# 03_-_POWER.net
KiCad netlist of a schematic drawn in Altium Designer
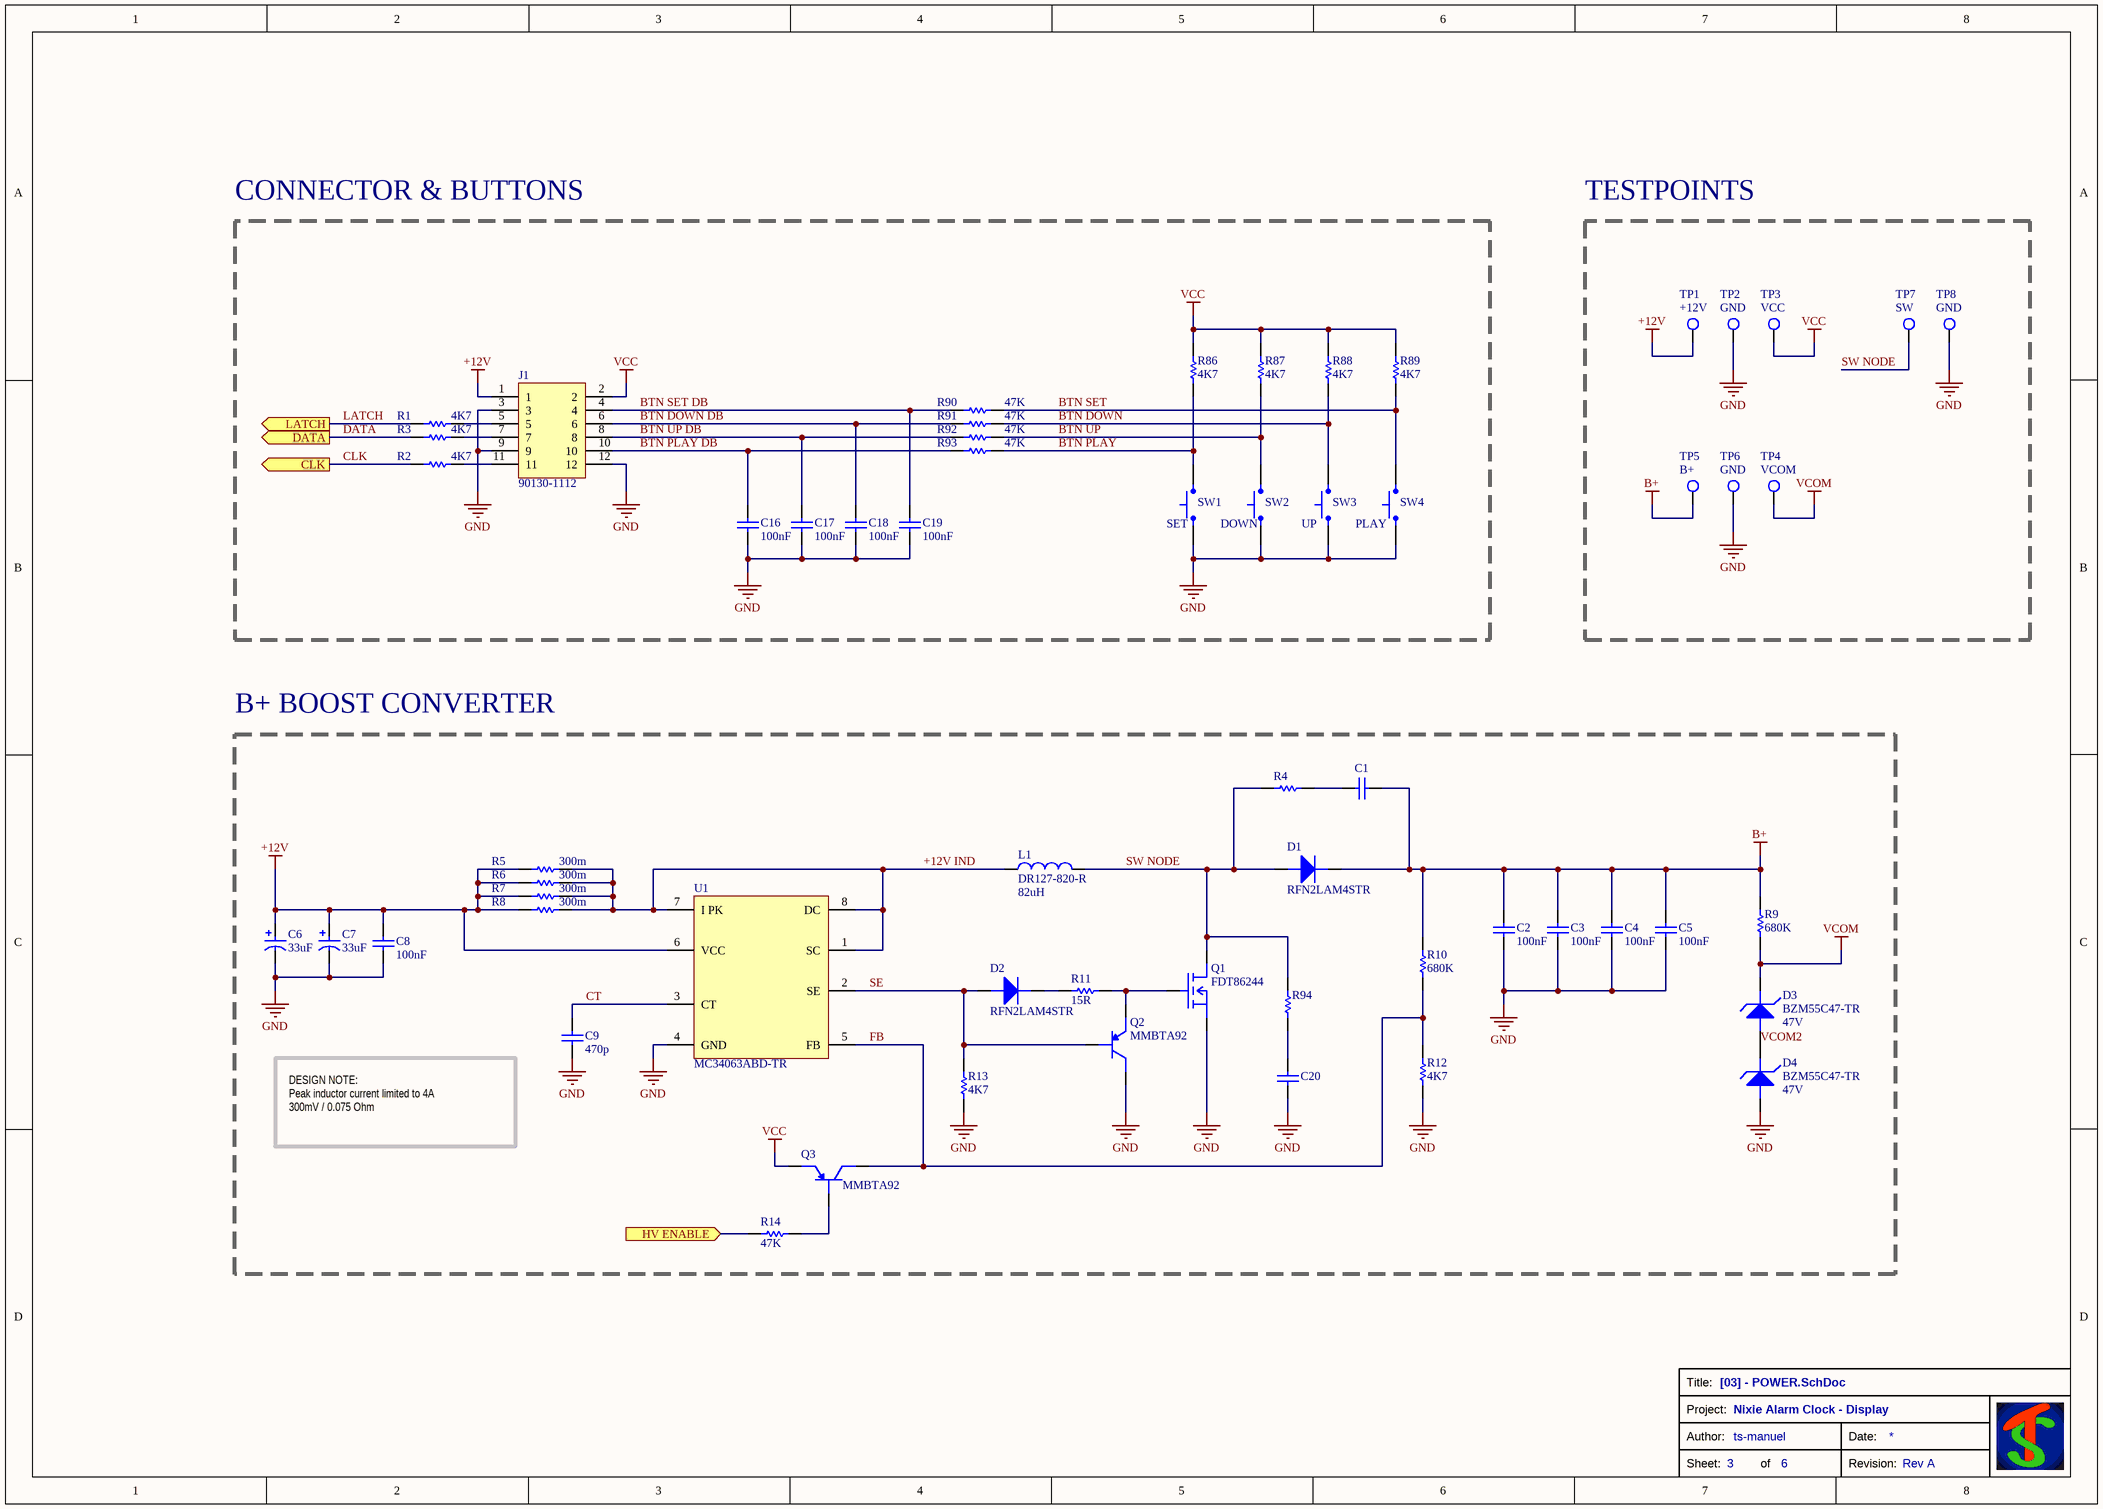
[diagram p0: [03] - POWER.SchDoc]

(export (version "E")
  (design (tool "Eeschema 10.0.6"))
  (components
    (comp (ref "C1")
      (value "885342208002")
      (footprint "CAP-1206")
      (description "Condensatori in ceramica multistrato MLCC - SMD/SMT WCAP-CSMH 200V 0.1uF 1206 10%")
      (fields (field (name "MANUFACTURER") "Wurth Elektronik") (field (name "TOLERANCE") "10%"))
      (libsource (lib "mt_local_library") (part "CAP-1206-100n-885342208002"))
    )
    (comp (ref "C2")
      (value "100nF")
      (footprint "CAP-1206")
      (description "Condensatori in ceramica multistrato MLCC - SMD/SMT WCAP-CSMH 200V 0.1uF 1206 10%")
      (fields (field (name "MANUFACTURER") "Wurth Elektronik") (field (name "TOLERANCE") "10%"))
      (libsource (lib "mt_local_library") (part "CAP-1206-100n-885342208002"))
    )
    (comp (ref "C3")
      (value "100nF")
      (footprint "CAP-1206")
      (description "Condensatori in ceramica multistrato MLCC - SMD/SMT WCAP-CSMH 200V 0.1uF 1206 10%")
      (fields (field (name "MANUFACTURER") "Wurth Elektronik") (field (name "TOLERANCE") "10%"))
      (libsource (lib "mt_local_library") (part "CAP-1206-100n-885342208002"))
    )
    (comp (ref "C4")
      (value "100nF")
      (footprint "CAP-1206")
      (description "Condensatori in ceramica multistrato MLCC - SMD/SMT WCAP-CSMH 200V 0.1uF 1206 10%")
      (fields (field (name "MANUFACTURER") "Wurth Elektronik") (field (name "TOLERANCE") "10%"))
      (libsource (lib "mt_local_library") (part "CAP-1206-100n-885342208002"))
    )
    (comp (ref "C5")
      (value "100nF")
      (footprint "CAP-1206")
      (description "Condensatori in ceramica multistrato MLCC - SMD/SMT WCAP-CSMH 200V 0.1uF 1206 10%")
      (fields (field (name "MANUFACTURER") "Wurth Elektronik") (field (name "TOLERANCE") "10%"))
      (libsource (lib "mt_local_library") (part "CAP-1206-100n-885342208002"))
    )
    (comp (ref "C6")
      (value "33uF")
      (footprint "CAPAE7366X60M")
      (description "Condensatori a polimeri organici in alluminio 40V 33uF 20% ESR=45mOhms")
      (fields (field (name "MANUFACTURER") "KEMET") (field (name "TOLERANCE") "20%"))
      (libsource (lib "mt_local_library") (part "CAP-CAN-33u-A768EB336M1GLAE045"))
    )
    (comp (ref "C7")
      (value "33uF")
      (footprint "CAPAE7366X60M")
      (description "Condensatori a polimeri organici in alluminio 40V 33uF 20% ESR=45mOhms")
      (fields (field (name "MANUFACTURER") "KEMET") (field (name "TOLERANCE") "20%"))
      (libsource (lib "mt_local_library") (part "CAP-CAN-33u-A768EB336M1GLAE045"))
    )
    (comp (ref "C8")
      (value "100nF")
      (footprint "CAP-1206")
      (description "Condensatori in ceramica multistrato MLCC - SMD/SMT WCAP-CSMH 200V 0.1uF 1206 10%")
      (fields (field (name "MANUFACTURER") "Wurth Elektronik") (field (name "TOLERANCE") "10%"))
      (libsource (lib "mt_local_library") (part "CAP-1206-100n-885342208002"))
    )
    (comp (ref "C9")
      (value "470p")
      (footprint "CAP-0805")
      (description "Condensatori in ceramica multistrato MLCC - SMD/SMT 0805 470pF 100volts C0G 5%")
      (fields (field (name "MANUFACTURER") "Wurth Elektronik") (field (name "TOLERANCE") "20%"))
      (libsource (lib "mt_local_library") (part "CAP-0805-470p-VJ0805A471JXBCW1BC"))
    )
    (comp (ref "C16")
      (value "100nF")
      (footprint "CAP-1206")
      (description "Condensatori in ceramica multistrato MLCC - SMD/SMT WCAP-CSMH 200V 0.1uF 1206 10%")
      (fields (field (name "MANUFACTURER") "Wurth Elektronik") (field (name "TOLERANCE") "10%"))
      (libsource (lib "mt_local_library") (part "CAP-1206-100n-885342208002"))
    )
    (comp (ref "C17")
      (value "100nF")
      (footprint "CAP-1206")
      (description "Condensatori in ceramica multistrato MLCC - SMD/SMT WCAP-CSMH 200V 0.1uF 1206 10%")
      (fields (field (name "MANUFACTURER") "Wurth Elektronik") (field (name "TOLERANCE") "10%"))
      (libsource (lib "mt_local_library") (part "CAP-1206-100n-885342208002"))
    )
    (comp (ref "C18")
      (value "100nF")
      (footprint "CAP-1206")
      (description "Condensatori in ceramica multistrato MLCC - SMD/SMT WCAP-CSMH 200V 0.1uF 1206 10%")
      (fields (field (name "MANUFACTURER") "Wurth Elektronik") (field (name "TOLERANCE") "10%"))
      (libsource (lib "mt_local_library") (part "CAP-1206-100n-885342208002"))
    )
    (comp (ref "C19")
      (value "100nF")
      (footprint "CAP-1206")
      (description "Condensatori in ceramica multistrato MLCC - SMD/SMT WCAP-CSMH 200V 0.1uF 1206 10%")
      (fields (field (name "MANUFACTURER") "Wurth Elektronik") (field (name "TOLERANCE") "10%"))
      (libsource (lib "mt_local_library") (part "CAP-1206-100n-885342208002"))
    )
    (comp (ref "C20")
      (value "885342208002")
      (footprint "CAP-1206")
      (description "Condensatori in ceramica multistrato MLCC - SMD/SMT WCAP-CSMH 200V 0.1uF 1206 10%")
      (fields (field (name "MANUFACTURER") "Wurth Elektronik") (field (name "TOLERANCE") "10%"))
      (libsource (lib "mt_local_library") (part "CAP-1206-100n-885342208002"))
    )
    (comp (ref "D1")
      (value "RFN2LAM4STR")
      (footprint "SODFL472X100-2M")
      (description "Diodi - Uso generico, alimentazione, commutazione 400V 1.5A Io PMDTM")
      (libsource (lib "mt_local_library") (part "DIODE-RFN2LAM4STR"))
    )
    (comp (ref "D2")
      (value "RFN2LAM4STR")
      (footprint "SODFL472X100-2M")
      (description "Diodi - Uso generico, alimentazione, commutazione 400V 1.5A Io PMDTM")
      (libsource (lib "mt_local_library") (part "DIODE-RFN2LAM4STR"))
    )
    (comp (ref "D3")
      (value "BZM55C47-TR")
      (footprint "DIOMELF1913M")
      (description "Diodi Zener 47 Volt 0.5W 5%")
      (fields (field (name "ZENER VOLTAGE") "47V"))
      (libsource (lib "mt_local_library") (part "ZENER-47V-BZM55C47-TR"))
    )
    (comp (ref "D4")
      (value "BZM55C47-TR")
      (footprint "DIOMELF1913M")
      (description "Diodi Zener 47 Volt 0.5W 5%")
      (fields (field (name "ZENER VOLTAGE") "47V"))
      (libsource (lib "mt_local_library") (part "ZENER-47V-BZM55C47-TR"))
    )
    (comp (ref "J1")
      (value "90130-1112")
      (footprint "SHDR12W65P254_2X6_1758X975X1110P")
      (description "Terminali e capicorda 2.54MM CGRIDIII HDR 12P V DR SHRD TIN")
      (libsource (lib "mt_local_library") (part "HEADER-12x2-2.54-TH-90130-1112"))
    )
    (comp (ref "L1")
      (value "DR127-820-R")
      (footprint "IND-DR127")
      (description "Induttori fissi 82uH 4.0A 0.143ohms")
      (fields
        (field (name "MANUFACTURER") "Taiyo Yuden")
        (field (name "TOLERANCE") "30%")
        (field (name "ALTIUM_VALUE") "82uH")
      )
      (libsource (lib "mt_local_library") (part "IND-DR127-82u"))
    )
    (comp (ref "Q1")
      (value "FDT86244")
      (footprint "SOT230P700X180-4M")
      (description "MOSFET 150V N-Channel PowerTrench MOSFET")
      (libsource (lib "mt_local_library") (part "NMOS-FDT86244"))
    )
    (comp (ref "Q2")
      (value "MMBTA92")
      (footprint "SOT95P240X110-3N")
      (description "300V PNP SMALL SIGNAL TRANSISTOR IN SOT23")
      (libsource (lib "mt_local_library") (part "PNP-MMBTA92"))
    )
    (comp (ref "Q3")
      (value "MMBTA92")
      (footprint "SOT95P240X110-3N")
      (description "300V PNP SMALL SIGNAL TRANSISTOR IN SOT23")
      (libsource (lib "mt_local_library") (part "PNP-MMBTA92"))
    )
    (comp (ref "R1")
      (value "4K7")
      (footprint "RES-0805")
      (description "Thin Film Resistors 4.7K ohm 1% 50 ppm")
      (fields (field (name "MANUFACTURER") "Yageo") (field (name "TOLERANCE") "1%"))
      (libsource (lib "mt_local_library") (part "RES-0805-4K7-RT0805FRE134K7L"))
    )
    (comp (ref "R2")
      (value "4K7")
      (footprint "RES-0805")
      (description "Thin Film Resistors 4.7K ohm 1% 50 ppm")
      (fields (field (name "MANUFACTURER") "Yageo") (field (name "TOLERANCE") "1%"))
      (libsource (lib "mt_local_library") (part "RES-0805-4K7-RT0805FRE134K7L"))
    )
    (comp (ref "R3")
      (value "4K7")
      (footprint "RES-0805")
      (description "Thin Film Resistors 4.7K ohm 1% 50 ppm")
      (fields (field (name "MANUFACTURER") "Yageo") (field (name "TOLERANCE") "1%"))
      (libsource (lib "mt_local_library") (part "RES-0805-4K7-RT0805FRE134K7L"))
    )
    (comp (ref "R4")
      (value "RT1206FRE07680KL")
      (footprint "RES-1206")
      (description "Thin Film Resistors 680K OHM 1% 50PPM 1/4W")
      (fields (field (name "MANUFACTURER") "Yageo") (field (name "TOLERANCE") "1%"))
      (libsource (lib "mt_local_library") (part "RES-1206-680K-RT1206FRE07680KL"))
    )
    (comp (ref "R5")
      (value "300m")
      (footprint "RES-0805")
      (description "Resistori a pellicola spessa - SMD 0805 0.25W 1% .30ohms AEC-Q200")
      (fields (field (name "MANUFACTURER") "Yageo") (field (name "TOLERANCE") "1%"))
      (libsource (lib "mt_local_library") (part "RES-0805-300m-ERJ-U6QFR30V"))
    )
    (comp (ref "R6")
      (value "300m")
      (footprint "RES-0805")
      (description "Resistori a pellicola spessa - SMD 0805 0.25W 1% .30ohms AEC-Q200")
      (fields (field (name "MANUFACTURER") "Yageo") (field (name "TOLERANCE") "1%"))
      (libsource (lib "mt_local_library") (part "RES-0805-300m-ERJ-U6QFR30V"))
    )
    (comp (ref "R7")
      (value "300m")
      (footprint "RES-0805")
      (description "Resistori a pellicola spessa - SMD 0805 0.25W 1% .30ohms AEC-Q200")
      (fields (field (name "MANUFACTURER") "Yageo") (field (name "TOLERANCE") "1%"))
      (libsource (lib "mt_local_library") (part "RES-0805-300m-ERJ-U6QFR30V"))
    )
    (comp (ref "R8")
      (value "300m")
      (footprint "RES-0805")
      (description "Resistori a pellicola spessa - SMD 0805 0.25W 1% .30ohms AEC-Q200")
      (fields (field (name "MANUFACTURER") "Yageo") (field (name "TOLERANCE") "1%"))
      (libsource (lib "mt_local_library") (part "RES-0805-300m-ERJ-U6QFR30V"))
    )
    (comp (ref "R9")
      (value "680K")
      (footprint "RES-1206")
      (description "Thin Film Resistors 680K OHM 1% 50PPM 1/4W")
      (fields (field (name "MANUFACTURER") "Yageo") (field (name "TOLERANCE") "1%"))
      (libsource (lib "mt_local_library") (part "RES-1206-680K-RT1206FRE07680KL"))
    )
    (comp (ref "R10")
      (value "680K")
      (footprint "RES-1206")
      (description "Thin Film Resistors 680K OHM 1% 50PPM 1/4W")
      (fields (field (name "MANUFACTURER") "Yageo") (field (name "TOLERANCE") "1%"))
      (libsource (lib "mt_local_library") (part "RES-1206-680K-RT1206FRE07680KL"))
    )
    (comp (ref "R11")
      (value "15R")
      (footprint "RES-0805")
      (description "Resistori a pellicola spessa - SMD 15ohm 5%")
      (fields (field (name "MANUFACTURER") "Bourns") (field (name "TOLERANCE") "5%"))
      (libsource (lib "mt_local_library") (part "RES-0805-15R-ERJ-CR0805-JW-150ELF"))
    )
    (comp (ref "R12")
      (value "4K7")
      (footprint "RES-0805")
      (description "Thin Film Resistors 4.7K ohm 1% 50 ppm")
      (fields (field (name "MANUFACTURER") "Yageo") (field (name "TOLERANCE") "1%"))
      (libsource (lib "mt_local_library") (part "RES-0805-4K7-RT0805FRE134K7L"))
    )
    (comp (ref "R13")
      (value "4K7")
      (footprint "RES-0805")
      (description "Thin Film Resistors 4.7K ohm 1% 50 ppm")
      (fields (field (name "MANUFACTURER") "Yageo") (field (name "TOLERANCE") "1%"))
      (libsource (lib "mt_local_library") (part "RES-0805-4K7-RT0805FRE134K7L"))
    )
    (comp (ref "R14")
      (value "47K")
      (footprint "RES-0805")
      (description "Thin Film Resistors 1/8W 47K ohm 1% 50ppm")
      (fields (field (name "MANUFACTURER") "Yageo") (field (name "TOLERANCE") "1%"))
      (libsource (lib "mt_local_library") (part "RES-0805-47K-RT0805FRE0747KL"))
    )
    (comp (ref "R86")
      (value "4K7")
      (footprint "RES-0805")
      (description "Thin Film Resistors 4.7K ohm 1% 50 ppm")
      (fields (field (name "MANUFACTURER") "Yageo") (field (name "TOLERANCE") "1%"))
      (libsource (lib "mt_local_library") (part "RES-0805-4K7-RT0805FRE134K7L"))
    )
    (comp (ref "R87")
      (value "4K7")
      (footprint "RES-0805")
      (description "Thin Film Resistors 4.7K ohm 1% 50 ppm")
      (fields (field (name "MANUFACTURER") "Yageo") (field (name "TOLERANCE") "1%"))
      (libsource (lib "mt_local_library") (part "RES-0805-4K7-RT0805FRE134K7L"))
    )
    (comp (ref "R88")
      (value "4K7")
      (footprint "RES-0805")
      (description "Thin Film Resistors 4.7K ohm 1% 50 ppm")
      (fields (field (name "MANUFACTURER") "Yageo") (field (name "TOLERANCE") "1%"))
      (libsource (lib "mt_local_library") (part "RES-0805-4K7-RT0805FRE134K7L"))
    )
    (comp (ref "R89")
      (value "4K7")
      (footprint "RES-0805")
      (description "Thin Film Resistors 4.7K ohm 1% 50 ppm")
      (fields (field (name "MANUFACTURER") "Yageo") (field (name "TOLERANCE") "1%"))
      (libsource (lib "mt_local_library") (part "RES-0805-4K7-RT0805FRE134K7L"))
    )
    (comp (ref "R90")
      (value "47K")
      (footprint "RES-0805")
      (description "Thin Film Resistors 1/8W 47K ohm 1% 50ppm")
      (fields (field (name "MANUFACTURER") "Yageo") (field (name "TOLERANCE") "1%"))
      (libsource (lib "mt_local_library") (part "RES-0805-47K-RT0805FRE0747KL"))
    )
    (comp (ref "R91")
      (value "47K")
      (footprint "RES-0805")
      (description "Thin Film Resistors 1/8W 47K ohm 1% 50ppm")
      (fields (field (name "MANUFACTURER") "Yageo") (field (name "TOLERANCE") "1%"))
      (libsource (lib "mt_local_library") (part "RES-0805-47K-RT0805FRE0747KL"))
    )
    (comp (ref "R92")
      (value "47K")
      (footprint "RES-0805")
      (description "Thin Film Resistors 1/8W 47K ohm 1% 50ppm")
      (fields (field (name "MANUFACTURER") "Yageo") (field (name "TOLERANCE") "1%"))
      (libsource (lib "mt_local_library") (part "RES-0805-47K-RT0805FRE0747KL"))
    )
    (comp (ref "R93")
      (value "47K")
      (footprint "RES-0805")
      (description "Thin Film Resistors 1/8W 47K ohm 1% 50ppm")
      (fields (field (name "MANUFACTURER") "Yageo") (field (name "TOLERANCE") "1%"))
      (libsource (lib "mt_local_library") (part "RES-0805-47K-RT0805FRE0747KL"))
    )
    (comp (ref "R94")
      (value "RT1206FRE07680KL")
      (footprint "RES-1206")
      (description "Thin Film Resistors 680K OHM 1% 50PPM 1/4W")
      (fields (field (name "MANUFACTURER") "Yageo") (field (name "TOLERANCE") "1%"))
      (libsource (lib "mt_local_library") (part "RES-1206-680K-RT1206FRE07680KL"))
    )
    (comp (ref "SW1")
      (value "SET")
      (footprint "Push Button 6mm TH")
      (libsource (lib "mt_local_library") (part "Push Button 6mm TH"))
    )
    (comp (ref "SW2")
      (value "DOWN")
      (footprint "Push Button 6mm TH")
      (libsource (lib "mt_local_library") (part "Push Button 6mm TH"))
    )
    (comp (ref "SW3")
      (value "UP")
      (footprint "Push Button 6mm TH")
      (libsource (lib "mt_local_library") (part "Push Button 6mm TH"))
    )
    (comp (ref "SW4")
      (value "PLAY")
      (footprint "Push Button 6mm TH")
      (libsource (lib "mt_local_library") (part "Push Button 6mm TH"))
    )
    (comp (ref "TP1")
      (value "+12V")
      (footprint "TESTPOINT-TH-1.3mm")
      (libsource (lib "mt_local_library") (part "TESTPOINT-TH-1.3mm"))
    )
    (comp (ref "TP2")
      (value "GND")
      (footprint "TESTPOINT-TH-1.3mm")
      (libsource (lib "mt_local_library") (part "TESTPOINT-TH-1.3mm"))
    )
    (comp (ref "TP3")
      (value "VCC")
      (footprint "TESTPOINT-TH-1.3mm")
      (libsource (lib "mt_local_library") (part "TESTPOINT-TH-1.3mm"))
    )
    (comp (ref "TP4")
      (value "VCOM")
      (footprint "TESTPOINT-TH-1.3mm")
      (libsource (lib "mt_local_library") (part "TESTPOINT-TH-1.3mm"))
    )
    (comp (ref "TP5")
      (value "B+")
      (footprint "TESTPOINT-TH-1.3mm")
      (libsource (lib "mt_local_library") (part "TESTPOINT-TH-1.3mm"))
    )
    (comp (ref "TP6")
      (value "GND")
      (footprint "TESTPOINT-TH-1.3mm")
      (libsource (lib "mt_local_library") (part "TESTPOINT-TH-1.3mm"))
    )
    (comp (ref "TP7")
      (value "SW")
      (footprint "TESTPOINT-TH-1.3mm")
      (libsource (lib "mt_local_library") (part "TESTPOINT-TH-1.3mm"))
    )
    (comp (ref "TP8")
      (value "GND")
      (footprint "TESTPOINT-TH-1.3mm")
      (libsource (lib "mt_local_library") (part "TESTPOINT-TH-1.3mm"))
    )
    (comp (ref "U1")
      (value "MC34063ABD-TR")
      (footprint "SOIC-8_3.9X4.9")
      (description "DC-DC Converter 3.0 to 40V")
      (libsource (lib "mt_local_library") (part "MC34063ABD-TR"))
    )
  )
  (nets
    (net (code "1") (name "+12V") (class "Default")
      (node (ref "C6") (pin "1") (pinfunction "P_1") (pintype "passive"))
      (node (ref "C7") (pin "1") (pinfunction "P_1") (pintype "passive"))
      (node (ref "C8") (pin "2") (pinfunction "2_2") (pintype "passive"))
      (node (ref "J1") (pin "1") (pinfunction "1_1") (pintype "passive"))
      (node (ref "R5") (pin "1") (pinfunction "1_1") (pintype "passive"))
      (node (ref "R6") (pin "1") (pinfunction "1_1") (pintype "passive"))
      (node (ref "R7") (pin "1") (pinfunction "1_1") (pintype "passive"))
      (node (ref "R8") (pin "1") (pinfunction "1_1") (pintype "passive"))
      (node (ref "TP1") (pin "1") (pinfunction "1_1") (pintype "passive"))
      (node (ref "U1") (pin "6") (pinfunction "VCC_6") (pintype "power_in"))
    )
    (net (code "2") (name "/+12V IND") (class "Default")
      (node (ref "L1") (pin "1") (pinfunction "1_1") (pintype "passive"))
      (node (ref "R5") (pin "2") (pinfunction "2_2") (pintype "passive"))
      (node (ref "R6") (pin "2") (pinfunction "2_2") (pintype "passive"))
      (node (ref "R7") (pin "2") (pinfunction "2_2") (pintype "passive"))
      (node (ref "R8") (pin "2") (pinfunction "2_2") (pintype "passive"))
      (node (ref "U1") (pin "1") (pinfunction "SC_1") (pintype "passive"))
      (node (ref "U1") (pin "7") (pinfunction "I_PK_7") (pintype "passive"))
      (node (ref "U1") (pin "8") (pinfunction "DC_8") (pintype "passive"))
    )
    (net (code "3") (name "/BTN DOWN") (class "Default")
      (node (ref "R88") (pin "1") (pinfunction "1_1") (pintype "passive"))
      (node (ref "R91") (pin "2") (pinfunction "2_2") (pintype "passive"))
      (node (ref "SW3") (pin "2") (pinfunction "2_2") (pintype "passive"))
    )
    (net (code "4") (name "/BTN DOWN DB") (class "Default")
      (node (ref "C18") (pin "2") (pinfunction "2_2") (pintype "passive"))
      (node (ref "J1") (pin "6") (pinfunction "6_6") (pintype "passive"))
      (node (ref "R91") (pin "1") (pinfunction "1_1") (pintype "passive"))
    )
    (net (code "5") (name "/BTN PLAY") (class "Default")
      (node (ref "R86") (pin "1") (pinfunction "1_1") (pintype "passive"))
      (node (ref "R93") (pin "2") (pinfunction "2_2") (pintype "passive"))
      (node (ref "SW1") (pin "2") (pinfunction "2_2") (pintype "passive"))
    )
    (net (code "6") (name "/BTN PLAY DB") (class "Default")
      (node (ref "C16") (pin "2") (pinfunction "2_2") (pintype "passive"))
      (node (ref "J1") (pin "10") (pinfunction "10_10") (pintype "passive"))
      (node (ref "R93") (pin "1") (pinfunction "1_1") (pintype "passive"))
    )
    (net (code "7") (name "/BTN SET") (class "Default")
      (node (ref "R89") (pin "1") (pinfunction "1_1") (pintype "passive"))
      (node (ref "R90") (pin "2") (pinfunction "2_2") (pintype "passive"))
      (node (ref "SW4") (pin "2") (pinfunction "2_2") (pintype "passive"))
    )
    (net (code "8") (name "/BTN SET DB") (class "Default")
      (node (ref "C19") (pin "2") (pinfunction "2_2") (pintype "passive"))
      (node (ref "J1") (pin "4") (pinfunction "4_4") (pintype "passive"))
      (node (ref "R90") (pin "1") (pinfunction "1_1") (pintype "passive"))
    )
    (net (code "9") (name "/BTN UP") (class "Default")
      (node (ref "R87") (pin "1") (pinfunction "1_1") (pintype "passive"))
      (node (ref "R92") (pin "2") (pinfunction "2_2") (pintype "passive"))
      (node (ref "SW2") (pin "2") (pinfunction "2_2") (pintype "passive"))
    )
    (net (code "10") (name "/BTN UP DB") (class "Default")
      (node (ref "C17") (pin "2") (pinfunction "2_2") (pintype "passive"))
      (node (ref "J1") (pin "8") (pinfunction "8_8") (pintype "passive"))
      (node (ref "R92") (pin "1") (pinfunction "1_1") (pintype "passive"))
    )
    (net (code "11") (name "/CLK") (class "Default")
      (node (ref "R2") (pin "1") (pinfunction "1_1") (pintype "passive"))
    )
    (net (code "12") (name "/CT") (class "Default")
      (node (ref "C9") (pin "2") (pinfunction "2_2") (pintype "passive"))
      (node (ref "U1") (pin "3") (pinfunction "CT_3") (pintype "passive"))
    )
    (net (code "13") (name "/DATA") (class "Default")
      (node (ref "R3") (pin "1") (pinfunction "1_1") (pintype "passive"))
    )
    (net (code "14") (name "/FB") (class "Default")
      (node (ref "Q3") (pin "3") (pinfunction "C_3") (pintype "passive"))
      (node (ref "R10") (pin "1") (pinfunction "1_1") (pintype "passive"))
      (node (ref "R12") (pin "2") (pinfunction "2_2") (pintype "passive"))
      (node (ref "U1") (pin "5") (pinfunction "FB_5") (pintype "passive"))
    )
    (net (code "15") (name "/HV ENABLE") (class "Default")
      (node (ref "R14") (pin "1") (pinfunction "1_1") (pintype "passive"))
    )
    (net (code "16") (name "/LATCH") (class "Default")
      (node (ref "R1") (pin "1") (pinfunction "1_1") (pintype "passive"))
    )
    (net (code "17") (name "/SE") (class "Default")
      (node (ref "D2") (pin "1") (pinfunction "A_1") (pintype "passive"))
      (node (ref "Q2") (pin "1") (pinfunction "B_1") (pintype "passive"))
      (node (ref "R13") (pin "2") (pinfunction "2_2") (pintype "passive"))
      (node (ref "U1") (pin "2") (pinfunction "SE_2") (pintype "passive"))
    )
    (net (code "18") (name "/SW NODE") (class "Default")
      (node (ref "D1") (pin "1") (pinfunction "A_1") (pintype "passive"))
      (node (ref "L1") (pin "2") (pinfunction "2_2") (pintype "passive"))
      (node (ref "Q1") (pin "2") (pinfunction "DRAIN_2") (pintype "passive"))
      (node (ref "R4") (pin "2") (pinfunction "2_2") (pintype "passive"))
      (node (ref "R94") (pin "2") (pinfunction "2_2") (pintype "passive"))
      (node (ref "TP7") (pin "1") (pinfunction "1_1") (pintype "passive"))
    )
    (net (code "19") (name "/VCOM2") (class "Default")
      (node (ref "D3") (pin "1") (pinfunction "A_1") (pintype "passive"))
      (node (ref "D4") (pin "2") (pinfunction "C_2") (pintype "passive"))
    )
    (net (code "20") (name "B+") (class "Default")
      (node (ref "C1") (pin "1") (pinfunction "1_1") (pintype "passive"))
      (node (ref "C2") (pin "2") (pinfunction "2_2") (pintype "passive"))
      (node (ref "C3") (pin "2") (pinfunction "2_2") (pintype "passive"))
      (node (ref "C4") (pin "2") (pinfunction "2_2") (pintype "passive"))
      (node (ref "C5") (pin "2") (pinfunction "2_2") (pintype "passive"))
      (node (ref "D1") (pin "2") (pinfunction "C_2") (pintype "passive"))
      (node (ref "R10") (pin "2") (pinfunction "2_2") (pintype "passive"))
      (node (ref "R9") (pin "2") (pinfunction "2_2") (pintype "passive"))
      (node (ref "TP5") (pin "1") (pinfunction "1_1") (pintype "passive"))
    )
    (net (code "21") (name "GND") (class "Default")
      (node (ref "C16") (pin "1") (pinfunction "1_1") (pintype "passive"))
      (node (ref "C17") (pin "1") (pinfunction "1_1") (pintype "passive"))
      (node (ref "C18") (pin "1") (pinfunction "1_1") (pintype "passive"))
      (node (ref "C19") (pin "1") (pinfunction "1_1") (pintype "passive"))
      (node (ref "C2") (pin "1") (pinfunction "1_1") (pintype "passive"))
      (node (ref "C20") (pin "1") (pinfunction "1_1") (pintype "passive"))
      (node (ref "C3") (pin "1") (pinfunction "1_1") (pintype "passive"))
      (node (ref "C4") (pin "1") (pinfunction "1_1") (pintype "passive"))
      (node (ref "C5") (pin "1") (pinfunction "1_1") (pintype "passive"))
      (node (ref "C6") (pin "2") (pinfunction "N_2") (pintype "passive"))
      (node (ref "C7") (pin "2") (pinfunction "N_2") (pintype "passive"))
      (node (ref "C8") (pin "1") (pinfunction "1_1") (pintype "passive"))
      (node (ref "C9") (pin "1") (pinfunction "1_1") (pintype "passive"))
      (node (ref "D4") (pin "1") (pinfunction "A_1") (pintype "passive"))
      (node (ref "J1") (pin "12") (pinfunction "12_12") (pintype "passive"))
      (node (ref "J1") (pin "3") (pinfunction "3_3") (pintype "passive"))
      (node (ref "J1") (pin "9") (pinfunction "9_9") (pintype "passive"))
      (node (ref "Q1") (pin "3") (pinfunction "SOURCE_3") (pintype "passive"))
      (node (ref "Q2") (pin "3") (pinfunction "C_3") (pintype "passive"))
      (node (ref "R12") (pin "1") (pinfunction "1_1") (pintype "passive"))
      (node (ref "R13") (pin "1") (pinfunction "1_1") (pintype "passive"))
      (node (ref "SW1") (pin "1") (pinfunction "1_1") (pintype "passive"))
      (node (ref "SW2") (pin "1") (pinfunction "1_1") (pintype "passive"))
      (node (ref "SW3") (pin "1") (pinfunction "1_1") (pintype "passive"))
      (node (ref "SW4") (pin "1") (pinfunction "1_1") (pintype "passive"))
      (node (ref "TP2") (pin "1") (pinfunction "1_1") (pintype "passive"))
      (node (ref "TP6") (pin "1") (pinfunction "1_1") (pintype "passive"))
      (node (ref "TP8") (pin "1") (pinfunction "1_1") (pintype "passive"))
      (node (ref "U1") (pin "4") (pinfunction "GND_4") (pintype "power_in"))
    )
    (net (code "22") (name "Net-(C1-Pad2)") (class "Default")
      (node (ref "C1") (pin "2") (pinfunction "2_2") (pintype "passive"))
      (node (ref "R4") (pin "1") (pinfunction "1_1") (pintype "passive"))
    )
    (net (code "23") (name "Net-(C20-Pad2)") (class "Default")
      (node (ref "C20") (pin "2") (pinfunction "2_2") (pintype "passive"))
      (node (ref "R94") (pin "1") (pinfunction "1_1") (pintype "passive"))
    )
    (net (code "24") (name "Net-(D2-C)") (class "Default")
      (node (ref "D2") (pin "2") (pinfunction "C_2") (pintype "passive"))
      (node (ref "R11") (pin "1") (pinfunction "1_1") (pintype "passive"))
    )
    (net (code "25") (name "Net-(J1-Pad5)") (class "Default")
      (node (ref "J1") (pin "5") (pinfunction "5_5") (pintype "passive"))
      (node (ref "R1") (pin "2") (pinfunction "2_2") (pintype "passive"))
    )
    (net (code "26") (name "Net-(J1-Pad7)") (class "Default")
      (node (ref "J1") (pin "7") (pinfunction "7_7") (pintype "passive"))
      (node (ref "R3") (pin "2") (pinfunction "2_2") (pintype "passive"))
    )
    (net (code "27") (name "Net-(J1-Pad11)") (class "Default")
      (node (ref "J1") (pin "11") (pinfunction "11_11") (pintype "passive"))
      (node (ref "R2") (pin "2") (pinfunction "2_2") (pintype "passive"))
    )
    (net (code "28") (name "Net-(Q1-GATE)") (class "Default")
      (node (ref "Q1") (pin "1") (pinfunction "GATE_1") (pintype "passive"))
      (node (ref "Q2") (pin "2") (pinfunction "E_2") (pintype "passive"))
      (node (ref "R11") (pin "2") (pinfunction "2_2") (pintype "passive"))
    )
    (net (code "29") (name "Net-(Q3-B)") (class "Default")
      (node (ref "Q3") (pin "1") (pinfunction "B_1") (pintype "passive"))
      (node (ref "R14") (pin "2") (pinfunction "2_2") (pintype "passive"))
    )
    (net (code "30") (name "VCC") (class "Default")
      (node (ref "J1") (pin "2") (pinfunction "2_2") (pintype "passive"))
      (node (ref "Q3") (pin "2") (pinfunction "E_2") (pintype "passive"))
      (node (ref "R86") (pin "2") (pinfunction "2_2") (pintype "passive"))
      (node (ref "R87") (pin "2") (pinfunction "2_2") (pintype "passive"))
      (node (ref "R88") (pin "2") (pinfunction "2_2") (pintype "passive"))
      (node (ref "R89") (pin "2") (pinfunction "2_2") (pintype "passive"))
      (node (ref "TP3") (pin "1") (pinfunction "1_1") (pintype "passive"))
    )
    (net (code "31") (name "VCOM") (class "Default")
      (node (ref "D3") (pin "2") (pinfunction "C_2") (pintype "passive"))
      (node (ref "R9") (pin "1") (pinfunction "1_1") (pintype "passive"))
      (node (ref "TP4") (pin "1") (pinfunction "1_1") (pintype "passive"))
    )
  )
)
